# NG2094_USB.net
KiCad netlist of a schematic drawn in Altium Designer
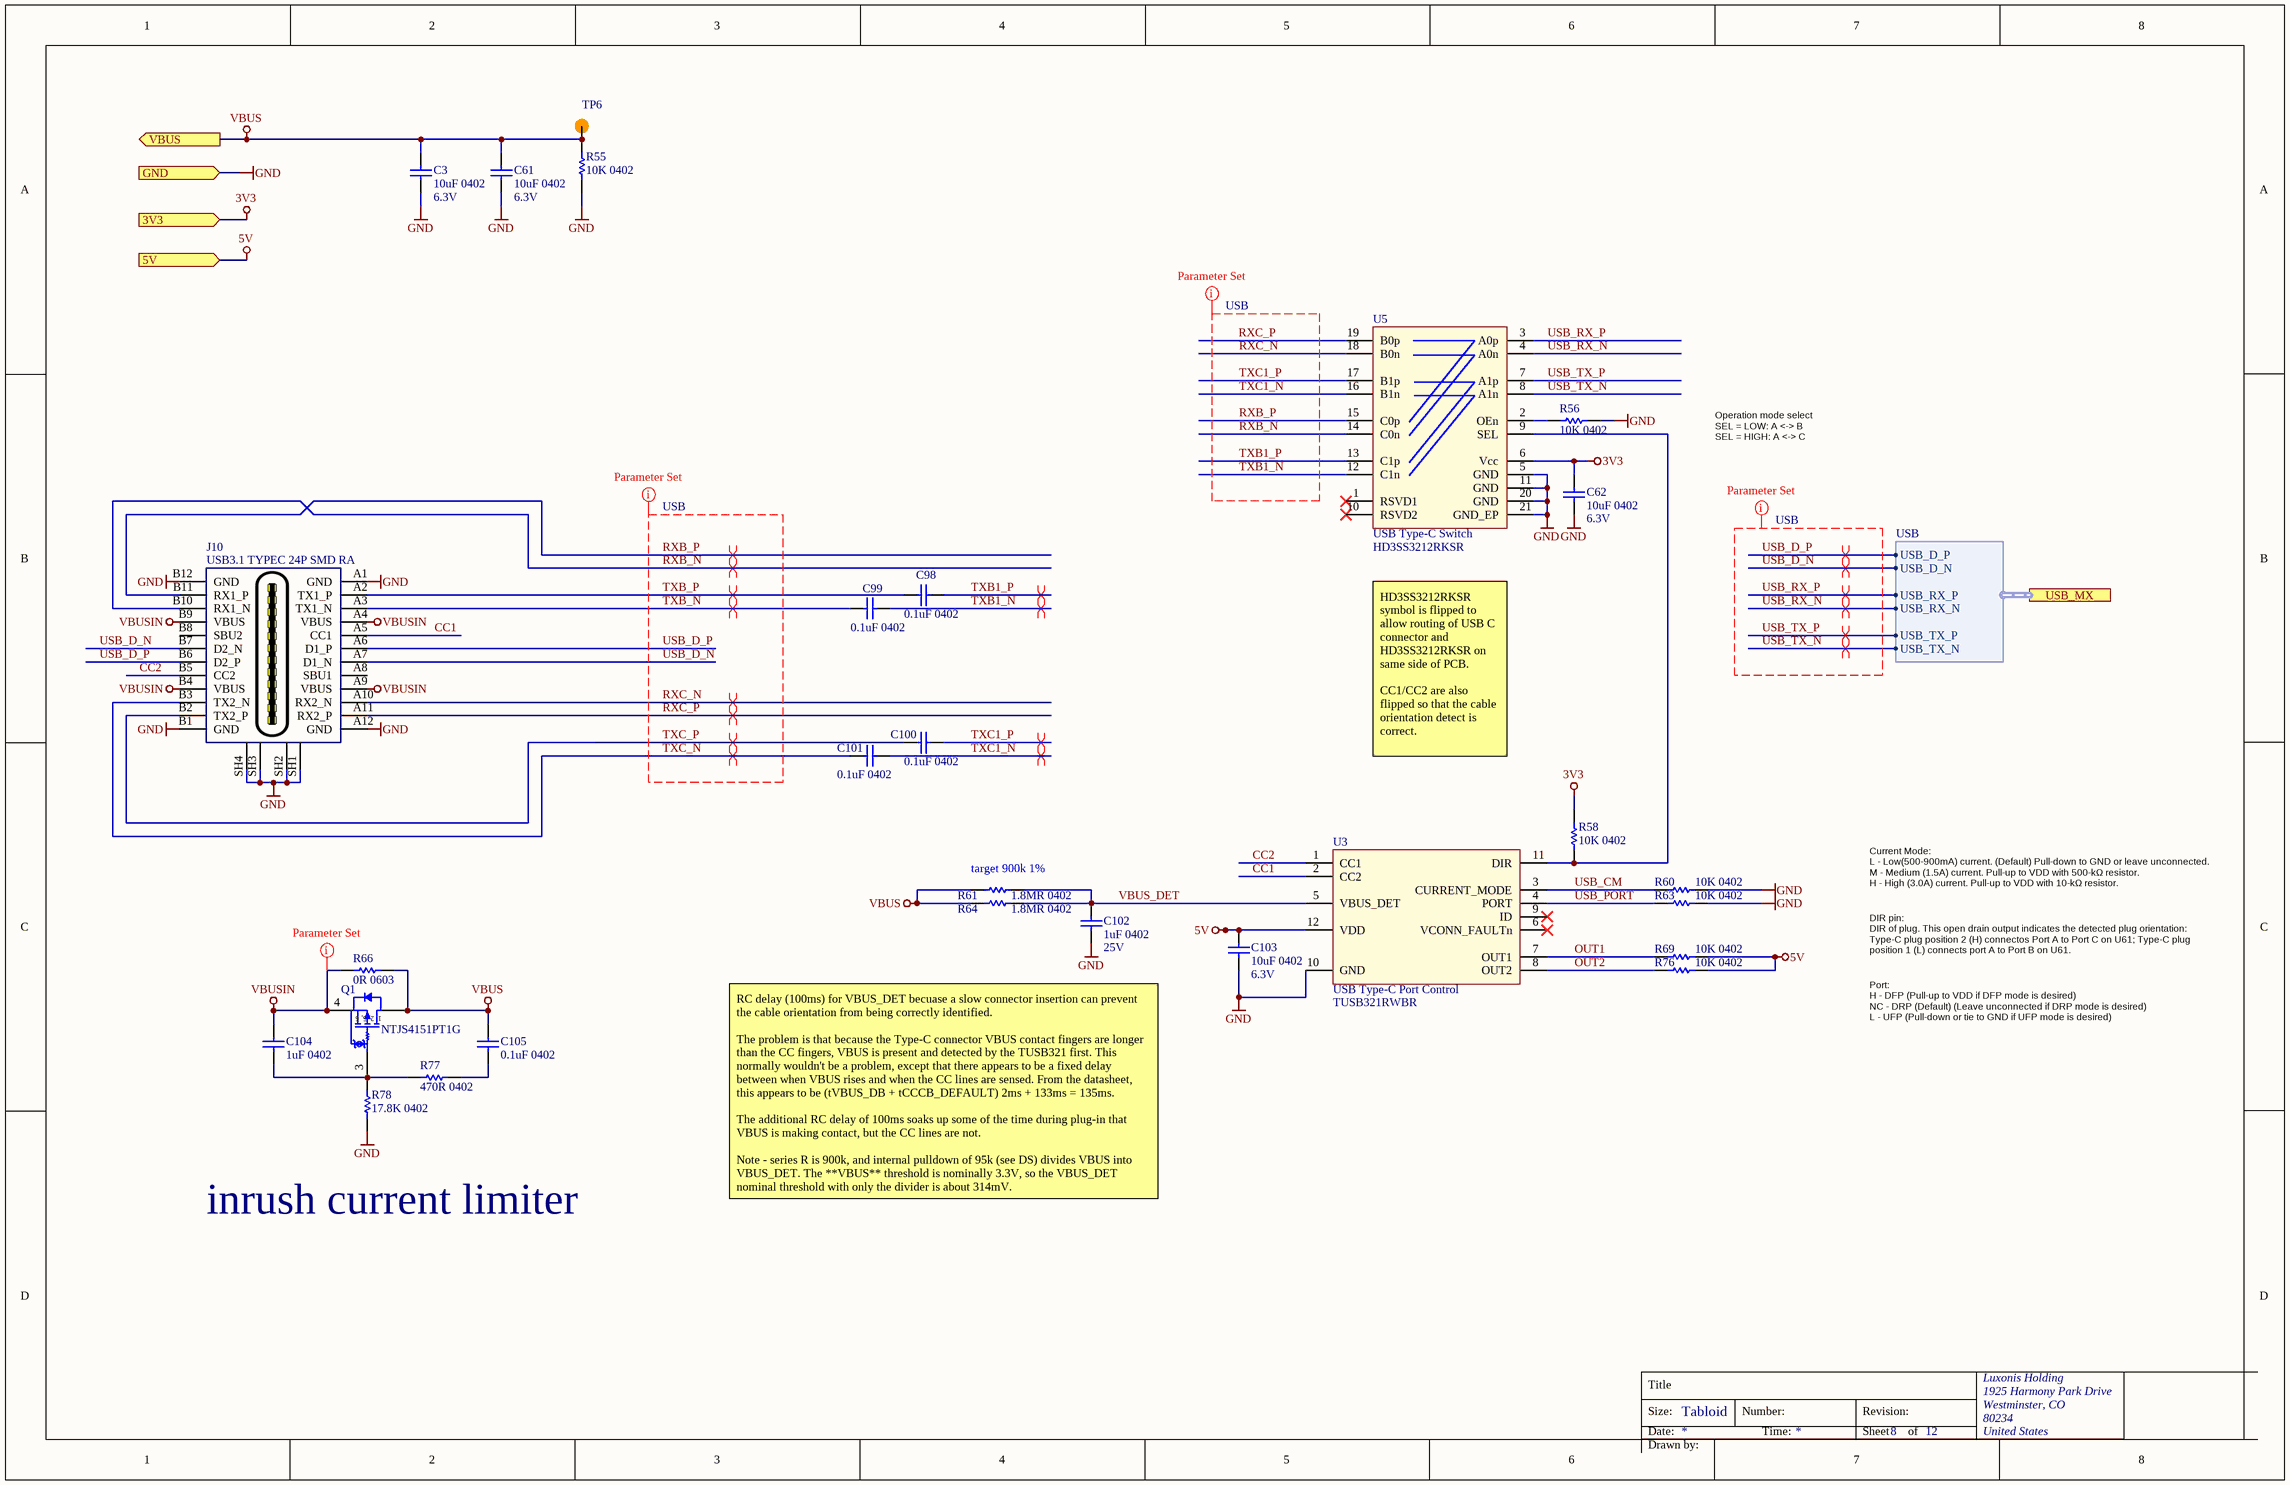
[diagram p0: NG2094_USB.SchDoc]

(export (version "E")
  (design (tool "Eeschema 10.0.6"))
  (components
    (comp (ref "C3")
      (value "10uF 0402")
      (footprint "CAP_Altium_Vault_Generic:CAPC0402(1005)70_L")
      (description "CAP CER 10UF 6.3V X5R 0402 20%")
      (fields (field (name "TOLERANCE") "20%") (field (name "VOLTAGE RATING") "6.3V"))
      (libsource (lib "LuxonisMaster") (part "GRM155R60J106ME15D"))
    )
    (comp (ref "C61")
      (value "10uF 0402")
      (footprint "CAP_Altium_Vault_Generic:CAPC0402(1005)70_L")
      (description "CAP CER 10UF 6.3V X5R 0402 20%")
      (fields (field (name "TOLERANCE") "20%") (field (name "VOLTAGE RATING") "6.3V"))
      (libsource (lib "LuxonisMaster") (part "GRM155R60J106ME15D"))
    )
    (comp (ref "C62")
      (value "10uF 0402")
      (footprint "CAP_Altium_Vault_Generic:CAPC0402(1005)70_L")
      (description "CAP CER 10UF 6.3V X5R 0402 20%")
      (fields (field (name "TOLERANCE") "20%") (field (name "VOLTAGE RATING") "6.3V"))
      (libsource (lib "LuxonisMaster") (part "GRM155R60J106ME15D"))
    )
    (comp (ref "C98")
      (value "0.1uF 0402")
      (footprint "CAP_Altium_Vault_Generic:CAPC0402(1005)70_L")
      (description "CAP CER 0.1UF 10V X7R 0402 5%")
      (fields (field (name "TOLERANCE") "5%"))
      (libsource (lib "LuxonisMaster") (part "GRM155R71A104JA01D"))
    )
    (comp (ref "C99")
      (value "0.1uF 0402")
      (footprint "CAP_Altium_Vault_Generic:CAPC0402(1005)70_L")
      (description "CAP CER 0.1UF 10V X7R 0402 5%")
      (fields (field (name "TOLERANCE") "5%"))
      (libsource (lib "LuxonisMaster") (part "GRM155R71A104JA01D"))
    )
    (comp (ref "C100")
      (value "0.1uF 0402")
      (footprint "CAP_Altium_Vault_Generic:CAPC0402(1005)70_L")
      (description "CAP CER 0.1UF 10V X7R 0402 5%")
      (fields (field (name "TOLERANCE") "5%"))
      (libsource (lib "LuxonisMaster") (part "GRM155R71A104JA01D"))
    )
    (comp (ref "C101")
      (value "0.1uF 0402")
      (footprint "CAP_Altium_Vault_Generic:CAPC0402(1005)70_L")
      (description "CAP CER 0.1UF 10V X7R 0402 5%")
      (fields (field (name "TOLERANCE") "5%"))
      (libsource (lib "LuxonisMaster") (part "GRM155R71A104JA01D"))
    )
    (comp (ref "C102")
      (value "1uF 0402")
      (footprint "CAP_Altium_Vault_Generic:CAPC0402(1005)70_L")
      (description "CAP CER 1UF 25V X5R 0402 10%")
      (fields
        (field (name "TOLERANCE") "10%")
        (field (name "VOLTAGE") "25V")
        (field (name "VOLTAGE RATING") "25V")
      )
      (libsource (lib "LuxonisMaster") (part "GRM155R61E105KA12D"))
    )
    (comp (ref "C103")
      (value "10uF 0402")
      (footprint "CAP_Altium_Vault_Generic:CAPC0402(1005)70_L")
      (description "CAP CER 10UF 6.3V X5R 0402 20%")
      (fields (field (name "TOLERANCE") "20%") (field (name "VOLTAGE RATING") "6.3V"))
      (libsource (lib "LuxonisMaster") (part "GRM155R60J106ME15D"))
    )
    (comp (ref "C104")
      (value "1uF 0402")
      (footprint "CAP_Altium_Vault_Generic:CAPC0402(1005)70_L")
      (description "CAP CER 1UF 25V X5R 0402 10%")
      (fields (field (name "TOLERANCE") "10%") (field (name "VOLTAGE") "25V"))
      (libsource (lib "LuxonisMaster") (part "GRM155R61E105KA12D"))
    )
    (comp (ref "C105")
      (value "0.1uF 0402")
      (footprint "CAP_Altium_Vault_Generic:CAPC0402(1005)70_L")
      (description "CAP CER 0.1UF 10V X7R 0402 5%")
      (fields (field (name "TOLERANCE") "5%"))
      (libsource (lib "LuxonisMaster") (part "GRM155R71A104JA01D"))
    )
    (comp (ref "J10")
      (value "USB3.1 TYPEC 24P SMD RA")
      (footprint "LuxonisMaster:105450-0101")
      (description "CONN RCP USB3.1 TYPEC 24P SMD RA")
      (libsource (lib "LuxonisMaster") (part "105450-0101"))
    )
    (comp (ref "Q1")
      (value "NTJS4151PT1G")
      (footprint "ONSC-SC70-6-419B-02_W_V")
      (description "Trench Power MOSFET, -20 V, -4.2 A, Single P-Channel, 6-Pin SC70, Pb-Free, Tape and Reel")
      (libsource (lib "NG2094") (part "NTJS4151PT1G"))
    )
    (comp (ref "R55")
      (value "10K 0402")
      (footprint "RES_Altium_Vault_Generic:RESC0402(1005)_L")
      (fields (field (name "TOLERANCE") "1%"))
      (libsource (lib "LuxonisMaster") (part "RC0402FR-1310KL"))
    )
    (comp (ref "R56")
      (value "10K 0402")
      (footprint "RES_Altium_Vault_Generic:RESC0402(1005)_L")
      (fields (field (name "TOLERANCE") "1%"))
      (libsource (lib "LuxonisMaster") (part "RC0402FR-1310KL"))
    )
    (comp (ref "R58")
      (value "10K 0402")
      (footprint "RES_Altium_Vault_Generic:RESC0402(1005)_L")
      (fields (field (name "TOLERANCE") "1%"))
      (libsource (lib "LuxonisMaster") (part "RC0402FR-1310KL"))
    )
    (comp (ref "R60")
      (value "10K 0402")
      (footprint "RES_Altium_Vault_Generic:RESC0402(1005)_L")
      (fields (field (name "TOLERANCE") "1%"))
      (libsource (lib "LuxonisMaster") (part "RC0402FR-1310KL"))
    )
    (comp (ref "R61")
      (value "1.8MR 0402")
      (footprint "RES_Altium_Vault_Generic:RESC0402(1005)_L")
      (description "RES SMD 1.8M OHM 1% 1/16W 0402")
      (fields (field (name "TOLERANCE") "1%"))
      (libsource (lib "LuxonisMaster") (part "CRCW04021M80FKED"))
    )
    (comp (ref "R63")
      (value "10K 0402")
      (footprint "RES_Altium_Vault_Generic:RESC0402(1005)_L")
      (fields (field (name "TOLERANCE") "1%"))
      (libsource (lib "LuxonisMaster") (part "RC0402FR-1310KL"))
    )
    (comp (ref "R64")
      (value "1.8MR 0402")
      (footprint "RES_Altium_Vault_Generic:RESC0402(1005)_L")
      (description "RES SMD 1.8M OHM 1% 1/16W 0402")
      (fields (field (name "TOLERANCE") "1%"))
      (libsource (lib "LuxonisMaster") (part "CRCW04021M80FKED"))
    )
    (comp (ref "R66")
      (value "0R 0603")
      (footprint "RES_Altium_Vault_Generic:RESC0603(1608)_L")
      (fields (field (name "TOLERANCE") "5%"))
      (libsource (lib "LuxonisMaster") (part "CRCW06030000Z0EA"))
    )
    (comp (ref "R69")
      (value "10K 0402")
      (footprint "RES_Altium_Vault_Generic:RESC0402(1005)_L")
      (fields (field (name "TOLERANCE") "1%"))
      (libsource (lib "LuxonisMaster") (part "RC0402FR-1310KL"))
    )
    (comp (ref "R76")
      (value "10K 0402")
      (footprint "RES_Altium_Vault_Generic:RESC0402(1005)_L")
      (fields (field (name "TOLERANCE") "1%"))
      (libsource (lib "LuxonisMaster") (part "RC0402FR-1310KL"))
    )
    (comp (ref "R77")
      (value "470R 0402")
      (footprint "RES_Altium_Vault_Generic:RESC0402(1005)_L")
      (description "RES SMD 470 OHM 1% 1/16W 0402")
      (fields (field (name "TOLERANCE") "1%"))
      (libsource (lib "LuxonisMaster") (part "CRCW0402470RFKED"))
    )
    (comp (ref "R78")
      (value "17.8K 0402")
      (footprint "RES_Altium_Vault_Generic:RESC0402(1005)_L")
      (fields (field (name "TOLERANCE") "1%"))
      (libsource (lib "LuxonisMaster") (part "ERJ-2RKF1782X"))
    )
    (comp (ref "TP6")
      (value "TP100_200_NS")
      (footprint "LuxonisMaster:TP100_200_NS")
      (libsource (lib "LuxonisMaster") (part "TEST_POINT"))
    )
    (comp (ref "U3")
      (value "USB Type-C Port Control")
      (footprint "LuxonisMaster:TUSB321RWBR")
      (description "IC USB PORT CONTROL TYPE-C 12X2Q")
      (fields (field (name "MANUFACTURER PART NUMBER 1") "TUSB321RWBR"))
      (libsource (lib "LuxonisMaster") (part "TUSB321RWBR"))
    )
    (comp (ref "U5")
      (value "USB Type-C Switch")
      (footprint "LuxonisMaster:HD3SS3212RKSR")
      (description "IC MUX 2:1 8 OHM 20VQFN")
      (fields (field (name "MANUFACTURER PART NUMBER 1") "HD3SS3212RKSR"))
      (libsource (lib "LuxonisMaster") (part "HD3SS3212RKSR"))
    )
  )
  (nets
    (net (code "2") (name "/CC1") (class "Default")
      (node (ref "J10") (pin "A5") (pinfunction "CC1_A5") (pintype "passive"))
      (node (ref "U3") (pin "2") (pinfunction "CC2_2") (pintype "passive"))
    )
    (net (code "3") (name "/CC2") (class "Default")
      (node (ref "J10") (pin "B5") (pinfunction "CC2_B5") (pintype "passive"))
      (node (ref "U3") (pin "1") (pinfunction "CC1_1") (pintype "passive"))
    )
    (net (code "4") (name "/OUT1") (class "Default")
      (node (ref "R69") (pin "1") (pinfunction "1_1") (pintype "passive"))
      (node (ref "U3") (pin "7") (pinfunction "OUT1_7") (pintype "passive"))
    )
    (net (code "5") (name "/OUT2") (class "Default")
      (node (ref "R76") (pin "1") (pinfunction "1_1") (pintype "passive"))
      (node (ref "U3") (pin "8") (pinfunction "OUT2_8") (pintype "passive"))
    )
    (net (code "6") (name "/RXB_N") (class "Default")
      (node (ref "J10") (pin "B10") (pinfunction "RX1_N_B10") (pintype "passive"))
      (node (ref "U5") (pin "14") (pinfunction "C0n_14") (pintype "passive"))
    )
    (net (code "7") (name "/RXB_P") (class "Default")
      (node (ref "J10") (pin "B11") (pinfunction "RX1_P_B11") (pintype "passive"))
      (node (ref "U5") (pin "15") (pinfunction "C0p_15") (pintype "passive"))
    )
    (net (code "8") (name "/RXC_N") (class "Default")
      (node (ref "J10") (pin "A10") (pinfunction "RX2_N_A10") (pintype "passive"))
      (node (ref "U5") (pin "18") (pinfunction "B0n_18") (pintype "passive"))
    )
    (net (code "9") (name "/RXC_P") (class "Default")
      (node (ref "J10") (pin "A11") (pinfunction "RX2_P_A11") (pintype "passive"))
      (node (ref "U5") (pin "19") (pinfunction "B0p_19") (pintype "passive"))
    )
    (net (code "10") (name "/TXB1_N") (class "Default")
      (node (ref "C99") (pin "2") (pinfunction "2_2") (pintype "passive"))
      (node (ref "U5") (pin "12") (pinfunction "C1n_12") (pintype "passive"))
    )
    (net (code "11") (name "/TXB1_P") (class "Default")
      (node (ref "C98") (pin "2") (pinfunction "2_2") (pintype "passive"))
      (node (ref "U5") (pin "13") (pinfunction "C1p_13") (pintype "passive"))
    )
    (net (code "12") (name "/TXB_N") (class "Default")
      (node (ref "C99") (pin "1") (pinfunction "1_1") (pintype "passive"))
      (node (ref "J10") (pin "A3") (pinfunction "TX1_N_A3") (pintype "passive"))
    )
    (net (code "13") (name "/TXB_P") (class "Default")
      (node (ref "C98") (pin "1") (pinfunction "1_1") (pintype "passive"))
      (node (ref "J10") (pin "A2") (pinfunction "TX1_P_A2") (pintype "passive"))
    )
    (net (code "14") (name "/TXC1_N") (class "Default")
      (node (ref "C101") (pin "2") (pinfunction "2_2") (pintype "passive"))
      (node (ref "U5") (pin "16") (pinfunction "B1n_16") (pintype "passive"))
    )
    (net (code "15") (name "/TXC1_P") (class "Default")
      (node (ref "C100") (pin "2") (pinfunction "2_2") (pintype "passive"))
      (node (ref "U5") (pin "17") (pinfunction "B1p_17") (pintype "passive"))
    )
    (net (code "16") (name "/TXC_N") (class "Default")
      (node (ref "C101") (pin "1") (pinfunction "1_1") (pintype "passive"))
      (node (ref "J10") (pin "B3") (pinfunction "TX2_N_B3") (pintype "passive"))
    )
    (net (code "17") (name "/TXC_P") (class "Default")
      (node (ref "C100") (pin "1") (pinfunction "1_1") (pintype "passive"))
      (node (ref "J10") (pin "B2") (pinfunction "TX2_P_B2") (pintype "passive"))
    )
    (net (code "18") (name "/USB_CM") (class "Default")
      (node (ref "R60") (pin "1") (pinfunction "1_1") (pintype "passive"))
      (node (ref "U3") (pin "3") (pinfunction "CURRENT_MODE_3") (pintype "passive"))
    )
    (net (code "19") (name "/USB_D_N") (class "Default")
      (node (ref "J10") (pin "A7") (pinfunction "D1_N_A7") (pintype "passive"))
      (node (ref "J10") (pin "B7") (pinfunction "D2_N_B7") (pintype "passive"))
    )
    (net (code "20") (name "/USB_D_P") (class "Default")
      (node (ref "J10") (pin "A6") (pinfunction "D1_P_A6") (pintype "passive"))
      (node (ref "J10") (pin "B6") (pinfunction "D2_P_B6") (pintype "passive"))
    )
    (net (code "21") (name "/USB_PORT") (class "Default")
      (node (ref "R63") (pin "1") (pinfunction "1_1") (pintype "passive"))
      (node (ref "U3") (pin "4") (pinfunction "PORT_4") (pintype "passive"))
    )
    (net (code "22") (name "/USB_RX_N") (class "Default")
      (node (ref "U5") (pin "4") (pinfunction "A0n_4") (pintype "passive"))
    )
    (net (code "23") (name "/USB_RX_P") (class "Default")
      (node (ref "U5") (pin "3") (pinfunction "A0p_3") (pintype "passive"))
    )
    (net (code "24") (name "/USB_TX_N") (class "Default")
      (node (ref "U5") (pin "8") (pinfunction "A1n_8") (pintype "passive"))
    )
    (net (code "25") (name "/USB_TX_P") (class "Default")
      (node (ref "U5") (pin "7") (pinfunction "A1p_7") (pintype "passive"))
    )
    (net (code "26") (name "/VBUS_DET") (class "Default")
      (node (ref "C102") (pin "2") (pinfunction "2_2") (pintype "passive"))
      (node (ref "R61") (pin "2") (pinfunction "2_2") (pintype "passive"))
      (node (ref "R64") (pin "2") (pinfunction "2_2") (pintype "passive"))
      (node (ref "U3") (pin "5") (pinfunction "VBUS_DET_5") (pintype "passive"))
    )
    (net (code "28") (name "3V3") (class "Default")
      (node (ref "C62") (pin "2") (pinfunction "2_2") (pintype "passive"))
      (node (ref "R58") (pin "2") (pinfunction "2_2") (pintype "passive"))
      (node (ref "U5") (pin "6") (pinfunction "Vcc_6") (pintype "passive"))
    )
    (net (code "29") (name "5V") (class "Default")
      (node (ref "C103") (pin "2") (pinfunction "2_2") (pintype "passive"))
      (node (ref "R69") (pin "2") (pinfunction "2_2") (pintype "passive"))
      (node (ref "R76") (pin "2") (pinfunction "2_2") (pintype "passive"))
      (node (ref "U3") (pin "12") (pinfunction "VDD_12") (pintype "passive"))
    )
    (net (code "30") (name "GND") (class "Default")
      (node (ref "C102") (pin "1") (pinfunction "1_1") (pintype "passive"))
      (node (ref "C103") (pin "1") (pinfunction "1_1") (pintype "passive"))
      (node (ref "C3") (pin "1") (pinfunction "1_1") (pintype "passive"))
      (node (ref "C61") (pin "1") (pinfunction "1_1") (pintype "passive"))
      (node (ref "C62") (pin "1") (pinfunction "1_1") (pintype "passive"))
      (node (ref "J10") (pin "A1") (pinfunction "GND_A1") (pintype "passive"))
      (node (ref "J10") (pin "A12") (pinfunction "GND_A12") (pintype "passive"))
      (node (ref "J10") (pin "B1") (pinfunction "GND_B1") (pintype "passive"))
      (node (ref "J10") (pin "B12") (pinfunction "GND_B12") (pintype "passive"))
      (node (ref "J10") (pin "SH1") (pinfunction "SH_SH1") (pintype "passive"))
      (node (ref "J10") (pin "SH2") (pinfunction "SH_SH2") (pintype "passive"))
      (node (ref "J10") (pin "SH3") (pinfunction "SH_SH3") (pintype "passive"))
      (node (ref "J10") (pin "SH4") (pinfunction "SH_SH4") (pintype "passive"))
      (node (ref "R55") (pin "1") (pinfunction "1_1") (pintype "passive"))
      (node (ref "R56") (pin "2") (pinfunction "2_2") (pintype "passive"))
      (node (ref "R60") (pin "2") (pinfunction "2_2") (pintype "passive"))
      (node (ref "R63") (pin "2") (pinfunction "2_2") (pintype "passive"))
      (node (ref "R78") (pin "1") (pinfunction "1_1") (pintype "passive"))
      (node (ref "U3") (pin "10") (pinfunction "GND_10") (pintype "passive"))
      (node (ref "U5") (pin "11") (pinfunction "GND_11") (pintype "passive"))
      (node (ref "U5") (pin "20") (pinfunction "GND_20") (pintype "passive"))
      (node (ref "U5") (pin "21") (pinfunction "GND_EP_21") (pintype "passive"))
      (node (ref "U5") (pin "5") (pinfunction "GND_5") (pintype "passive"))
    )
    (net (code "31") (name "Net-(C105-Pad1)") (class "Default")
      (node (ref "C105") (pin "1") (pinfunction "1_1") (pintype "passive"))
      (node (ref "R77") (pin "2") (pinfunction "2_2") (pintype "passive"))
    )
    (net (code "32") (name "Net-(Q1-G)") (class "Default")
      (node (ref "C104") (pin "1") (pinfunction "1_1") (pintype "passive"))
      (node (ref "Q1") (pin "3") (pinfunction "G_3") (pintype "passive"))
      (node (ref "R77") (pin "1") (pinfunction "1_1") (pintype "passive"))
      (node (ref "R78") (pin "2") (pinfunction "2_2") (pintype "passive"))
    )
    (net (code "33") (name "Net-(U3-DIR)") (class "Default")
      (node (ref "R58") (pin "1") (pinfunction "1_1") (pintype "passive"))
      (node (ref "U3") (pin "11") (pinfunction "DIR_11") (pintype "passive"))
      (node (ref "U5") (pin "9") (pinfunction "SEL_9") (pintype "passive"))
    )
    (net (code "34") (name "Net-(U5-OEn)") (class "Default")
      (node (ref "R56") (pin "1") (pinfunction "1_1") (pintype "passive"))
      (node (ref "U5") (pin "2") (pinfunction "OEn_2") (pintype "passive"))
    )
    (net (code "35") (name "VBUS") (class "Default")
      (node (ref "C105") (pin "2") (pinfunction "2_2") (pintype "passive"))
      (node (ref "C3") (pin "2") (pinfunction "2_2") (pintype "passive"))
      (node (ref "C61") (pin "2") (pinfunction "2_2") (pintype "passive"))
      (node (ref "Q1") (pin "1") (pinfunction "D_1") (pintype "passive"))
      (node (ref "Q1") (pin "2") (pinfunction "D_2") (pintype "passive"))
      (node (ref "Q1") (pin "5") (pinfunction "D_5") (pintype "passive"))
      (node (ref "Q1") (pin "6") (pinfunction "D_6") (pintype "passive"))
      (node (ref "R55") (pin "2") (pinfunction "2_2") (pintype "passive"))
      (node (ref "R61") (pin "1") (pinfunction "1_1") (pintype "passive"))
      (node (ref "R64") (pin "1") (pinfunction "1_1") (pintype "passive"))
      (node (ref "R66") (pin "2") (pinfunction "2_2") (pintype "passive"))
      (node (ref "TP6") (pin "1") (pintype "passive"))
    )
    (net (code "36") (name "VBUSIN") (class "Default")
      (node (ref "C104") (pin "2") (pinfunction "2_2") (pintype "passive"))
      (node (ref "J10") (pin "A4") (pinfunction "VBUS_A4") (pintype "passive"))
      (node (ref "J10") (pin "A9") (pinfunction "VBUS_A9") (pintype "passive"))
      (node (ref "J10") (pin "B4") (pinfunction "VBUS_B4") (pintype "passive"))
      (node (ref "J10") (pin "B9") (pinfunction "VBUS_B9") (pintype "passive"))
      (node (ref "Q1") (pin "4") (pinfunction "S_4") (pintype "passive"))
      (node (ref "R66") (pin "1") (pinfunction "1_1") (pintype "passive"))
    )
    (net (code "37") (name "unconnected-(J10-SBU1-PadA8)") (class "Default")
      (node (ref "J10") (pin "A8") (pinfunction "SBU1_A8") (pintype "passive"))
    )
    (net (code "38") (name "unconnected-(J10-SBU2-PadB8)") (class "Default")
      (node (ref "J10") (pin "B8") (pinfunction "SBU2_B8") (pintype "passive"))
    )
    (net (code "39") (name "unconnected-(U3-ID-Pad9)") (class "Default")
      (node (ref "U3") (pin "9") (pinfunction "ID_9") (pintype "passive+no_connect"))
    )
    (net (code "40") (name "unconnected-(U3-VCONN_FAULTn-Pad6)") (class "Default")
      (node (ref "U3") (pin "6") (pinfunction "VCONN_FAULTn_6") (pintype "passive+no_connect"))
    )
    (net (code "41") (name "unconnected-(U5-RSVD1-Pad1)") (class "Default")
      (node (ref "U5") (pin "1") (pinfunction "RSVD1_1") (pintype "passive+no_connect"))
    )
    (net (code "42") (name "unconnected-(U5-RSVD2-Pad10)") (class "Default")
      (node (ref "U5") (pin "10") (pinfunction "RSVD2_10") (pintype "passive+no_connect"))
    )
  )
)
